# StandBy_converter.net
KiCad netlist of a schematic drawn in Altium Designer
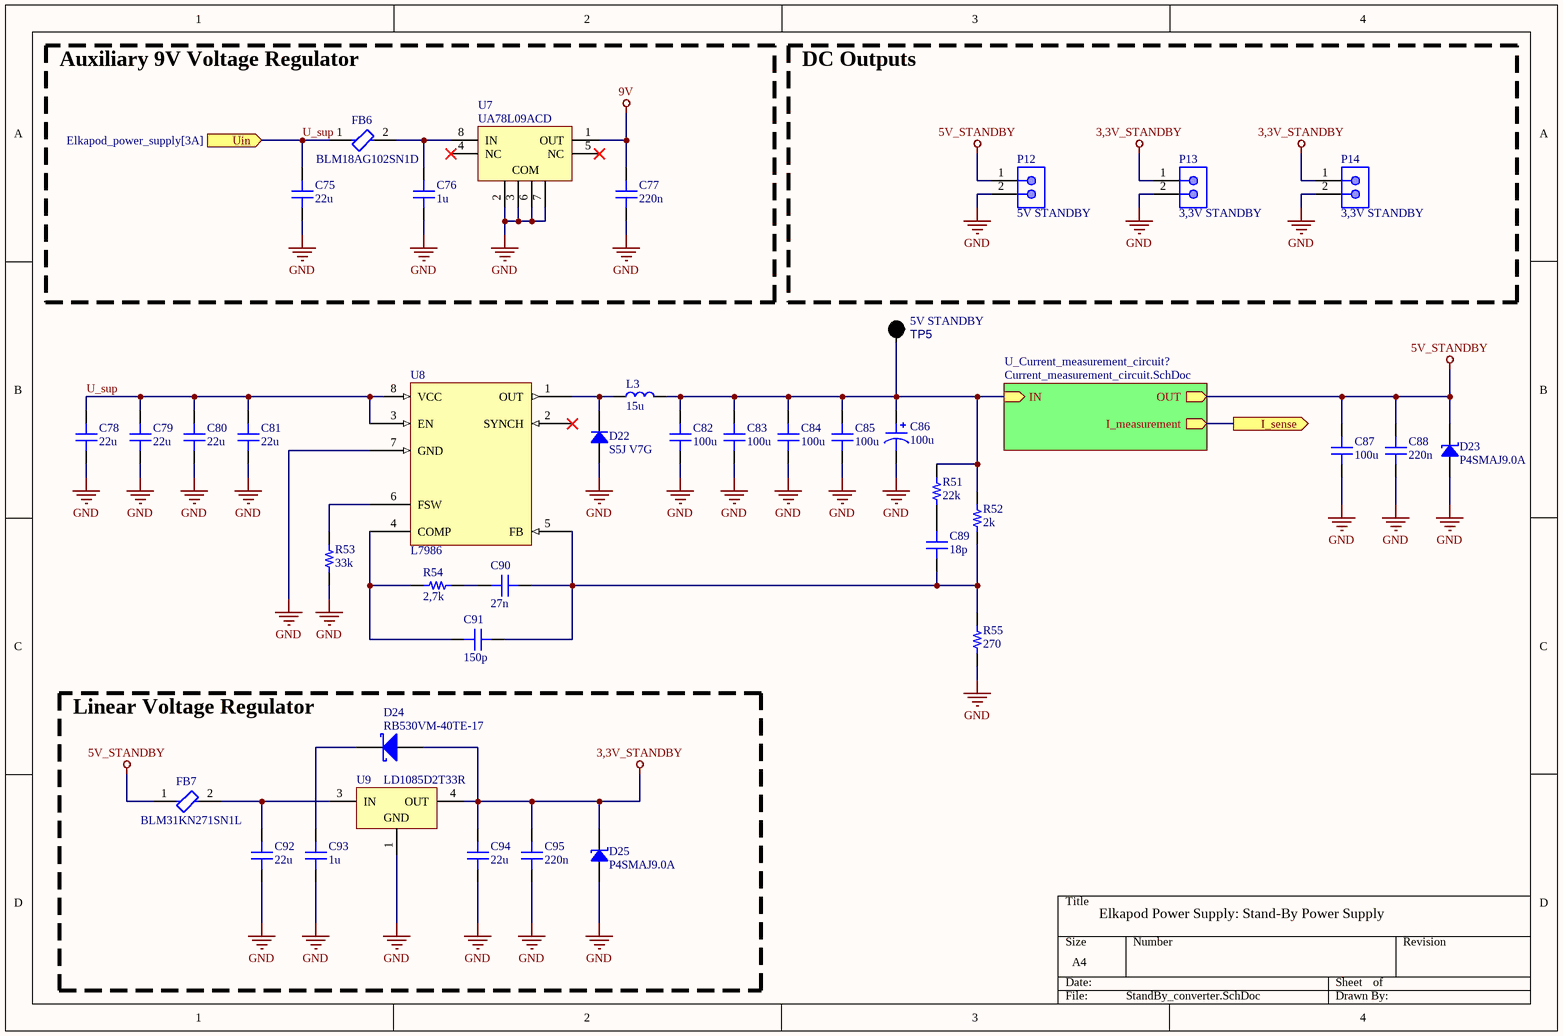
[diagram p0: StandBy_converter.SchDoc]

(export (version "E")
  (design (tool "Eeschema 10.0.6"))
  (components
    (comp (ref "C75")
      (value "22u")
      (footprint "CAP 0805_2012")
      (description "CAP CER 22UF 25V X7R 0805")
      (fields
        (field (name "PART NUMBER") "VJ0805Y684KXQTW1BC")
        (field (name "MANUFACTURER") "Vishay Vitramon")
      )
      (libsource (lib "Celestial Altium Library - altium_library") (part "Capacitor"))
    )
    (comp (ref "C76")
      (value "1u")
      (footprint "CAP 0603_1608")
      (description "CAP CER 1uF 25V X5R 0603")
      (fields (field (name "PART NUMBER") "C0603C272F3GAC7867") (field (name "MANUFACTURER") "KEMET"))
      (libsource (lib "Celestial Altium Library - altium_library") (part "Capacitor"))
    )
    (comp (ref "C77")
      (value "220n")
      (footprint "CAP 0603_1608")
      (description "CAP CER 220nF 25V X5R 0603")
      (fields (field (name "PART NUMBER") "C0603C272F3GAC7867") (field (name "MANUFACTURER") "KEMET"))
      (libsource (lib "Celestial Altium Library - altium_library") (part "Capacitor"))
    )
    (comp (ref "C78")
      (value "22u")
      (footprint "CAP 0805_2012")
      (description "CAP CER 22UF 25V X7R 0805")
      (fields
        (field (name "PART NUMBER") "VJ0805Y684KXQTW1BC")
        (field (name "MANUFACTURER") "Vishay Vitramon")
      )
      (libsource (lib "Celestial Altium Library - altium_library") (part "Capacitor"))
    )
    (comp (ref "C79")
      (value "22u")
      (footprint "CAP 0805_2012")
      (description "CAP CER 22UF 25V X7R 0805")
      (fields
        (field (name "PART NUMBER") "VJ0805Y684KXQTW1BC")
        (field (name "MANUFACTURER") "Vishay Vitramon")
      )
      (libsource (lib "Celestial Altium Library - altium_library") (part "Capacitor"))
    )
    (comp (ref "C80")
      (value "22u")
      (footprint "CAP 0805_2012")
      (description "CAP CER 22UF 25V X7R 0805")
      (fields
        (field (name "PART NUMBER") "VJ0805Y684KXQTW1BC")
        (field (name "MANUFACTURER") "Vishay Vitramon")
      )
      (libsource (lib "Celestial Altium Library - altium_library") (part "Capacitor"))
    )
    (comp (ref "C81")
      (value "22u")
      (footprint "CAP 0805_2012")
      (description "CAP CER 22UF 25V X7R 0805")
      (fields
        (field (name "PART NUMBER") "VJ0805Y684KXQTW1BC")
        (field (name "MANUFACTURER") "Vishay Vitramon")
      )
      (libsource (lib "Celestial Altium Library - altium_library") (part "Capacitor"))
    )
    (comp (ref "C82")
      (value "100u")
      (footprint "CAP 1210_3225 - 1MM")
      (description "CAP CER 1210 100UF 10V X7R")
      (fields (field (name "PART NUMBER") "CAN13X104KARAC7800") (field (name "MANUFACTURER") "KEMET"))
      (libsource (lib "Celestial Altium Library - altium_library") (part "Capacitor"))
    )
    (comp (ref "C83")
      (value "100u")
      (footprint "CAP 1210_3225 - 1MM")
      (description "CAP CER 1210 100UF 10V X7R")
      (fields (field (name "PART NUMBER") "CAN13X104KARAC7800") (field (name "MANUFACTURER") "KEMET"))
      (libsource (lib "Celestial Altium Library - altium_library") (part "Capacitor"))
    )
    (comp (ref "C84")
      (value "100u")
      (footprint "CAP 1210_3225 - 1MM")
      (description "CAP CER 1210 100UF 10V X7R")
      (fields (field (name "PART NUMBER") "CAN13X104KARAC7800") (field (name "MANUFACTURER") "KEMET"))
      (libsource (lib "Celestial Altium Library - altium_library") (part "Capacitor"))
    )
    (comp (ref "C85")
      (value "100u")
      (footprint "CAP 1210_3225 - 1MM")
      (description "CAP CER 1210 100UF 10V X7R")
      (fields (field (name "PART NUMBER") "CAN13X104KARAC7800") (field (name "MANUFACTURER") "KEMET"))
      (libsource (lib "Celestial Altium Library - altium_library") (part "Capacitor"))
    )
    (comp (ref "C86")
      (value "100u")
      (footprint "CAP ALSMD 8.3MM H10.5MM")
      (description "UCD1V101MNL1GS; CAP ALUM 100UF 20% 16V SMD")
      (libsource (lib "Celestial Altium Library - altium_library") (part "Polarised Capacitor"))
    )
    (comp (ref "C87")
      (value "100u")
      (footprint "CAP 1210_3225 - 1MM")
      (description "CAP CER 1210 100UF 10V X7R")
      (fields (field (name "PART NUMBER") "CAN13X104KARAC7800") (field (name "MANUFACTURER") "KEMET"))
      (libsource (lib "Celestial Altium Library - altium_library") (part "Capacitor"))
    )
    (comp (ref "C88")
      (value "220n")
      (footprint "CAP 0603_1608")
      (description "CAP CER 220nF 25V X5R 0603")
      (fields (field (name "PART NUMBER") "C0603C272F3GAC7867") (field (name "MANUFACTURER") "KEMET"))
      (libsource (lib "Celestial Altium Library - altium_library") (part "Capacitor"))
    )
    (comp (ref "C89")
      (value "18p")
      (footprint "CAP 0603_1608")
      (description "CAP CER 18pF 50V G0C 0603")
      (fields (field (name "PART NUMBER") "C0603C272F3GAC7867") (field (name "MANUFACTURER") "KEMET"))
      (libsource (lib "Celestial Altium Library - altium_library") (part "Capacitor"))
    )
    (comp (ref "C90")
      (value "27n")
      (footprint "CAP 0603_1608")
      (description "CAP CER 27nF 50V G0C 0603")
      (fields (field (name "PART NUMBER") "C0603C272F3GAC7867") (field (name "MANUFACTURER") "KEMET"))
      (libsource (lib "Celestial Altium Library - altium_library") (part "Capacitor"))
    )
    (comp (ref "C91")
      (value "150p")
      (footprint "CAP 0603_1608")
      (description "CAP CER 150pF 50V G0C 0603")
      (fields (field (name "PART NUMBER") "C0603C272F3GAC7867") (field (name "MANUFACTURER") "KEMET"))
      (libsource (lib "Celestial Altium Library - altium_library") (part "Capacitor"))
    )
    (comp (ref "C92")
      (value "22u")
      (footprint "CAP 0805_2012")
      (description "CAP CER 22UF 25V X7R 0805")
      (fields
        (field (name "PART NUMBER") "VJ0805Y684KXQTW1BC")
        (field (name "MANUFACTURER") "Vishay Vitramon")
      )
      (libsource (lib "Celestial Altium Library - altium_library") (part "Capacitor"))
    )
    (comp (ref "C93")
      (value "1u")
      (footprint "CAP 0603_1608")
      (description "CAP CER 1uF 25V X5R 0603")
      (fields (field (name "PART NUMBER") "C0603C272F3GAC7867") (field (name "MANUFACTURER") "KEMET"))
      (libsource (lib "Celestial Altium Library - altium_library") (part "Capacitor"))
    )
    (comp (ref "C94")
      (value "22u")
      (footprint "CAP 0805_2012")
      (description "CAP CER 22UF 25V X7R 0805")
      (fields
        (field (name "PART NUMBER") "VJ0805Y684KXQTW1BC")
        (field (name "MANUFACTURER") "Vishay Vitramon")
      )
      (libsource (lib "Celestial Altium Library - altium_library") (part "Capacitor"))
    )
    (comp (ref "C95")
      (value "220n")
      (footprint "CAP 0603_1608")
      (description "CAP CER 220nF 25V X5R 0603")
      (fields (field (name "PART NUMBER") "C0603C272F3GAC7867") (field (name "MANUFACTURER") "KEMET"))
      (libsource (lib "Celestial Altium Library - altium_library") (part "Capacitor"))
    )
    (comp (ref "D22")
      (value "S5J V7G")
      (footprint "DO214AB SMC")
      (description "DIODE GEN PURP 600V 5A DO214AB")
      (fields (field (name "MANUFACTURER") "Taiwan Semiconductor Corporation"))
      (libsource (lib "Celestial Altium Library - altium_library") (part "Diode"))
    )
    (comp (ref "D23")
      (value "P4SMAJ9.0A")
      (footprint "DO214AC SMA")
      (description "TVS DIODE 9VDC DO214AC")
      (libsource (lib "Celestial Altium Library - altium_library") (part "DIODE TVS UNI"))
    )
    (comp (ref "D24")
      (value "RB530VM-40TE-17")
      (footprint "SOD-323")
      (description "Schottky diode; 0,1A; 40V")
      (fields (field (name "PUBLISHER") "Altium Limited"))
      (libsource (lib "Infineon Discrete Diode") (part "BAS140W"))
    )
    (comp (ref "D25")
      (value "P4SMAJ9.0A")
      (footprint "DO214AC SMA")
      (description "TVS DIODE 9VDC DO214AC")
      (libsource (lib "Celestial Altium Library - altium_library") (part "DIODE TVS UNI"))
    )
    (comp (ref "FB6")
      (value "BLM18AG102SN1D")
      (footprint "FP-BLM18-0_15-t0_8-MFG")
      (description "Chip Ferrite Bead, 0603, 1000Ω @ 100MHz, 0.5Ω, 25%, 450mA")
      (fields (field (name "TOLERANCE") "25%"))
      (libsource (lib "Altium Content Vault") (part "5f30dd21d616792df468990f7003faa"))
    )
    (comp (ref "FB7")
      (value "BLM31KN271SN1L")
      (footprint "FP-BLM31-0_2-t1_6-d3_3-MFG")
      (description "Chip Ferrite Bead, 1206, 270Ω @ 100MHz, 0.016Ω, 25%, 4.5A")
      (libsource (lib "Altium Content Vault") (part "5f30dd21d616792df468990f7003faa"))
    )
    (comp (ref "L3")
      (value "15u")
      (footprint "12,5x12,5_INDUCTOR")
      (description "SMD power inductor; Imax = 4,27A; Isat = 5,69A")
      (libsource (lib "My_passive_components") (part "12,5x12,5_INDUCTOR"))
    )
    (comp (ref "P12")
      (value "5V STANDBY")
      (footprint "MOLX-22-23-2021_V")
      (fields (field (name "PARTNUMBER") "22-23-2021"))
      (libsource (lib "Altium Content Vault") (part "CN-1P-M-R2"))
    )
    (comp (ref "P13")
      (value "3,3V STANDBY")
      (footprint "MOLX-22-23-2021_V")
      (fields (field (name "PARTNUMBER") "22-23-2021"))
      (libsource (lib "Altium Content Vault") (part "CN-1P-M-R2"))
    )
    (comp (ref "P14")
      (value "3,3V STANDBY")
      (footprint "MOLX-22-23-2021_V")
      (fields (field (name "PARTNUMBER") "22-23-2021"))
      (libsource (lib "Altium Content Vault") (part "CN-1P-M-R2"))
    )
    (comp (ref "R51")
      (value "22k")
      (footprint "RES 0603_1608")
      (description "RES 22K OHM 1% 0,1W 0603")
      (fields
        (field (name "PART NUMBER") "RNCS0603BKE10K0")
        (field (name "MANUFACTURER") "Stackpole Electronics Inc")
      )
      (libsource (lib "Celestial Altium Library - altium_library") (part "Resistor"))
    )
    (comp (ref "R52")
      (value "2k")
      (footprint "RES 0603_1608")
      (description "RES 2K OHM 1% 0,1W 0603")
      (fields
        (field (name "PART NUMBER") "RNCS0603BKE10K0")
        (field (name "MANUFACTURER") "Stackpole Electronics Inc")
      )
      (libsource (lib "Celestial Altium Library - altium_library") (part "Resistor"))
    )
    (comp (ref "R53")
      (value "33k")
      (footprint "RES 0603_1608")
      (description "RES 33K OHM 1% 0,1W 0603")
      (fields
        (field (name "PART NUMBER") "RNCS0603BKE10K0")
        (field (name "MANUFACTURER") "Stackpole Electronics Inc")
      )
      (libsource (lib "Celestial Altium Library - altium_library") (part "Resistor"))
    )
    (comp (ref "R54")
      (value "2,7k")
      (footprint "RES 0603_1608")
      (description "RES 2,7K OHM 1% 0,1W 0603")
      (fields
        (field (name "PART NUMBER") "RNCS0603BKE10K0")
        (field (name "MANUFACTURER") "Stackpole Electronics Inc")
      )
      (libsource (lib "Celestial Altium Library - altium_library") (part "Resistor"))
    )
    (comp (ref "R55")
      (value "270")
      (footprint "RES 0603_1608")
      (description "RES 270 OHM 1% 0,1W 0603")
      (fields
        (field (name "PART NUMBER") "RNCS0603BKE10K0")
        (field (name "MANUFACTURER") "Stackpole Electronics Inc")
      )
      (libsource (lib "Celestial Altium Library - altium_library") (part "Resistor"))
    )
    (comp (ref "TP5")
      (value "5V STANDBY")
      (footprint "Keystone_5006_BLACK")
      (description "Keystone 5006 Test Point (BLACK)")
      (libsource (lib "test_points") (part "Keystone 5006 Test Point"))
    )
    (comp (ref "U7")
      (value "UA78L09ACD")
      (footprint "D0008A_N")
      (fields (field (name "MANUFACTURER") "Texas Instruments"))
      (libsource (lib "Altium Content Vault") (part "TI-UA78L09AD8"))
    )
    (comp (ref "U8")
      (value "L7986")
      (footprint "HSOP8_L")
      (description "3 A step-down switching regulator; HSOP8")
      (libsource (lib "My_DC_converters") (part "L7986"))
    )
    (comp (ref "U9")
      (value "LD1085D2T33R")
      (footprint "TO-263_M")
      (description "3A, Low Drop Positive Voltage Regulator, 3.3V, 3-Pin D2PAK")
      (libsource (lib "Altium Content Vault") (part "PM-REG-LD1085-SOT3"))
    )
  )
  (nets
    (net (code "1") (name "/IN") (class "Default")
      (node (ref "C82") (pin "2") (pinfunction "2_2") (pintype "passive"))
      (node (ref "C83") (pin "2") (pinfunction "2_2") (pintype "passive"))
      (node (ref "C84") (pin "2") (pinfunction "2_2") (pintype "passive"))
      (node (ref "C85") (pin "2") (pinfunction "2_2") (pintype "passive"))
      (node (ref "C86") (pin "1") (pinfunction "1_1") (pintype "passive"))
      (node (ref "L3") (pin "2") (pinfunction "2_2") (pintype "passive"))
      (node (ref "R51") (pin "2") (pinfunction "2_2") (pintype "passive"))
      (node (ref "R52") (pin "2") (pinfunction "2_2") (pintype "passive"))
      (node (ref "TP5") (pin "0") (pinfunction "0_0") (pintype "passive"))
    )
    (net (code "3") (name "/U_sup") (class "Default")
      (node (ref "C75") (pin "2") (pinfunction "2_2") (pintype "passive"))
      (node (ref "C78") (pin "2") (pinfunction "2_2") (pintype "passive"))
      (node (ref "C79") (pin "2") (pinfunction "2_2") (pintype "passive"))
      (node (ref "C80") (pin "2") (pinfunction "2_2") (pintype "passive"))
      (node (ref "C81") (pin "2") (pinfunction "2_2") (pintype "passive"))
      (node (ref "FB6") (pin "1") (pinfunction "1_1") (pintype "passive"))
      (node (ref "U8") (pin "3") (pinfunction "EN_3") (pintype "input"))
      (node (ref "U8") (pin "8") (pinfunction "VCC_8") (pintype "input"))
    )
    (net (code "4") (name "3,3V_STANDBY") (class "Default")
      (node (ref "C94") (pin "2") (pinfunction "2_2") (pintype "passive"))
      (node (ref "C95") (pin "2") (pinfunction "2_2") (pintype "passive"))
      (node (ref "D24") (pin "2") (pinfunction "A_2") (pintype "passive"))
      (node (ref "D25") (pin "2") (pinfunction "2_2") (pintype "passive"))
      (node (ref "P13") (pin "1") (pinfunction "1_1") (pintype "passive"))
      (node (ref "P14") (pin "1") (pinfunction "1_1") (pintype "passive"))
      (node (ref "U9") (pin "4") (pinfunction "OUT_4") (pintype "power_in"))
    )
    (net (code "5") (name "5V_STANDBY") (class "Default")
      (node (ref "C87") (pin "2") (pinfunction "2_2") (pintype "passive"))
      (node (ref "C88") (pin "2") (pinfunction "2_2") (pintype "passive"))
      (node (ref "D23") (pin "2") (pinfunction "2_2") (pintype "passive"))
      (node (ref "FB7") (pin "1") (pinfunction "1_1") (pintype "passive"))
      (node (ref "P12") (pin "1") (pinfunction "1_1") (pintype "passive"))
    )
    (net (code "6") (name "9V") (class "Default")
      (node (ref "C77") (pin "2") (pinfunction "2_2") (pintype "passive"))
      (node (ref "U7") (pin "1") (pinfunction "OUT_1") (pintype "power_in"))
    )
    (net (code "7") (name "GND") (class "Default")
      (node (ref "C75") (pin "1") (pinfunction "1_1") (pintype "passive"))
      (node (ref "C76") (pin "1") (pinfunction "1_1") (pintype "passive"))
      (node (ref "C77") (pin "1") (pinfunction "1_1") (pintype "passive"))
      (node (ref "C78") (pin "1") (pinfunction "1_1") (pintype "passive"))
      (node (ref "C79") (pin "1") (pinfunction "1_1") (pintype "passive"))
      (node (ref "C80") (pin "1") (pinfunction "1_1") (pintype "passive"))
      (node (ref "C81") (pin "1") (pinfunction "1_1") (pintype "passive"))
      (node (ref "C82") (pin "1") (pinfunction "1_1") (pintype "passive"))
      (node (ref "C83") (pin "1") (pinfunction "1_1") (pintype "passive"))
      (node (ref "C84") (pin "1") (pinfunction "1_1") (pintype "passive"))
      (node (ref "C85") (pin "1") (pinfunction "1_1") (pintype "passive"))
      (node (ref "C86") (pin "2") (pinfunction "2_2") (pintype "passive"))
      (node (ref "C87") (pin "1") (pinfunction "1_1") (pintype "passive"))
      (node (ref "C88") (pin "1") (pinfunction "1_1") (pintype "passive"))
      (node (ref "C92") (pin "1") (pinfunction "1_1") (pintype "passive"))
      (node (ref "C93") (pin "1") (pinfunction "1_1") (pintype "passive"))
      (node (ref "C94") (pin "1") (pinfunction "1_1") (pintype "passive"))
      (node (ref "C95") (pin "1") (pinfunction "1_1") (pintype "passive"))
      (node (ref "D22") (pin "1") (pinfunction "1_1") (pintype "passive"))
      (node (ref "D23") (pin "1") (pinfunction "1_1") (pintype "passive"))
      (node (ref "D25") (pin "1") (pinfunction "1_1") (pintype "passive"))
      (node (ref "P12") (pin "2") (pinfunction "2_2") (pintype "passive"))
      (node (ref "P13") (pin "2") (pinfunction "2_2") (pintype "passive"))
      (node (ref "P14") (pin "2") (pinfunction "2_2") (pintype "passive"))
      (node (ref "R53") (pin "1") (pinfunction "1_1") (pintype "passive"))
      (node (ref "R55") (pin "1") (pinfunction "1_1") (pintype "passive"))
      (node (ref "U7") (pin "2") (pinfunction "GND_2") (pintype "power_in"))
      (node (ref "U7") (pin "3") (pinfunction "GND_3") (pintype "power_in"))
      (node (ref "U7") (pin "6") (pinfunction "GND_6") (pintype "power_in"))
      (node (ref "U7") (pin "7") (pinfunction "GND_7") (pintype "power_in"))
      (node (ref "U8") (pin "7") (pinfunction "GND_7") (pintype "input"))
      (node (ref "U9") (pin "1") (pinfunction "GND_1") (pintype "power_in"))
    )
    (net (code "8") (name "Net-(C89-Pad2)") (class "Default")
      (node (ref "C89") (pin "2") (pinfunction "2_2") (pintype "passive"))
      (node (ref "R51") (pin "1") (pinfunction "1_1") (pintype "passive"))
    )
    (net (code "9") (name "Net-(C90-Pad2)") (class "Default")
      (node (ref "C90") (pin "2") (pinfunction "2_2") (pintype "passive"))
      (node (ref "R54") (pin "1") (pinfunction "1_1") (pintype "passive"))
    )
    (net (code "10") (name "Net-(D24-K)") (class "Default")
      (node (ref "C93") (pin "2") (pinfunction "2_2") (pintype "passive"))
      (node (ref "D24") (pin "1") (pinfunction "K_1") (pintype "passive"))
    )
    (net (code "11") (name "Net-(U7-IN)") (class "Default")
      (node (ref "C76") (pin "2") (pinfunction "2_2") (pintype "passive"))
      (node (ref "FB6") (pin "2") (pinfunction "2_2") (pintype "passive"))
      (node (ref "U7") (pin "8") (pinfunction "IN_8") (pintype "power_in"))
    )
    (net (code "12") (name "Net-(U8-COMP)") (class "Default")
      (node (ref "C91") (pin "2") (pinfunction "2_2") (pintype "passive"))
      (node (ref "R54") (pin "2") (pinfunction "2_2") (pintype "passive"))
      (node (ref "U8") (pin "4") (pinfunction "COMP_4") (pintype "passive"))
    )
    (net (code "13") (name "Net-(U8-FB)") (class "Default")
      (node (ref "C89") (pin "1") (pinfunction "1_1") (pintype "passive"))
      (node (ref "C90") (pin "1") (pinfunction "1_1") (pintype "passive"))
      (node (ref "C91") (pin "1") (pinfunction "1_1") (pintype "passive"))
      (node (ref "R52") (pin "1") (pinfunction "1_1") (pintype "passive"))
      (node (ref "R55") (pin "2") (pinfunction "2_2") (pintype "passive"))
      (node (ref "U8") (pin "5") (pinfunction "FB_5") (pintype "input"))
    )
    (net (code "14") (name "Net-(U8-FSW)") (class "Default")
      (node (ref "R53") (pin "2") (pinfunction "2_2") (pintype "passive"))
      (node (ref "U8") (pin "6") (pinfunction "FSW_6") (pintype "passive"))
    )
    (net (code "15") (name "Net-(U8-OUT)") (class "Default")
      (node (ref "D22") (pin "2") (pinfunction "2_2") (pintype "passive"))
      (node (ref "L3") (pin "1") (pinfunction "1_1") (pintype "passive"))
      (node (ref "U8") (pin "1") (pinfunction "OUT_1") (pintype "output"))
    )
    (net (code "16") (name "Net-(U9-IN)") (class "Default")
      (node (ref "C92") (pin "2") (pinfunction "2_2") (pintype "passive"))
      (node (ref "FB7") (pin "2") (pinfunction "2_2") (pintype "passive"))
      (node (ref "U9") (pin "3") (pinfunction "IN_3") (pintype "power_in"))
    )
    (net (code "17") (name "unconnected-(U7-NC-Pad4)") (class "Default")
      (node (ref "U7") (pin "4") (pinfunction "NC_4") (pintype "passive+no_connect"))
    )
    (net (code "18") (name "unconnected-(U7-NC-Pad5)") (class "Default")
      (node (ref "U7") (pin "5") (pinfunction "NC_5") (pintype "passive+no_connect"))
    )
    (net (code "19") (name "unconnected-(U8-SYNCH-Pad2)") (class "Default")
      (node (ref "U8") (pin "2") (pinfunction "SYNCH_2") (pintype "input+no_connect"))
    )
  )
)
